# SensorNode.net
KiCad netlist of a schematic drawn in EAGLE
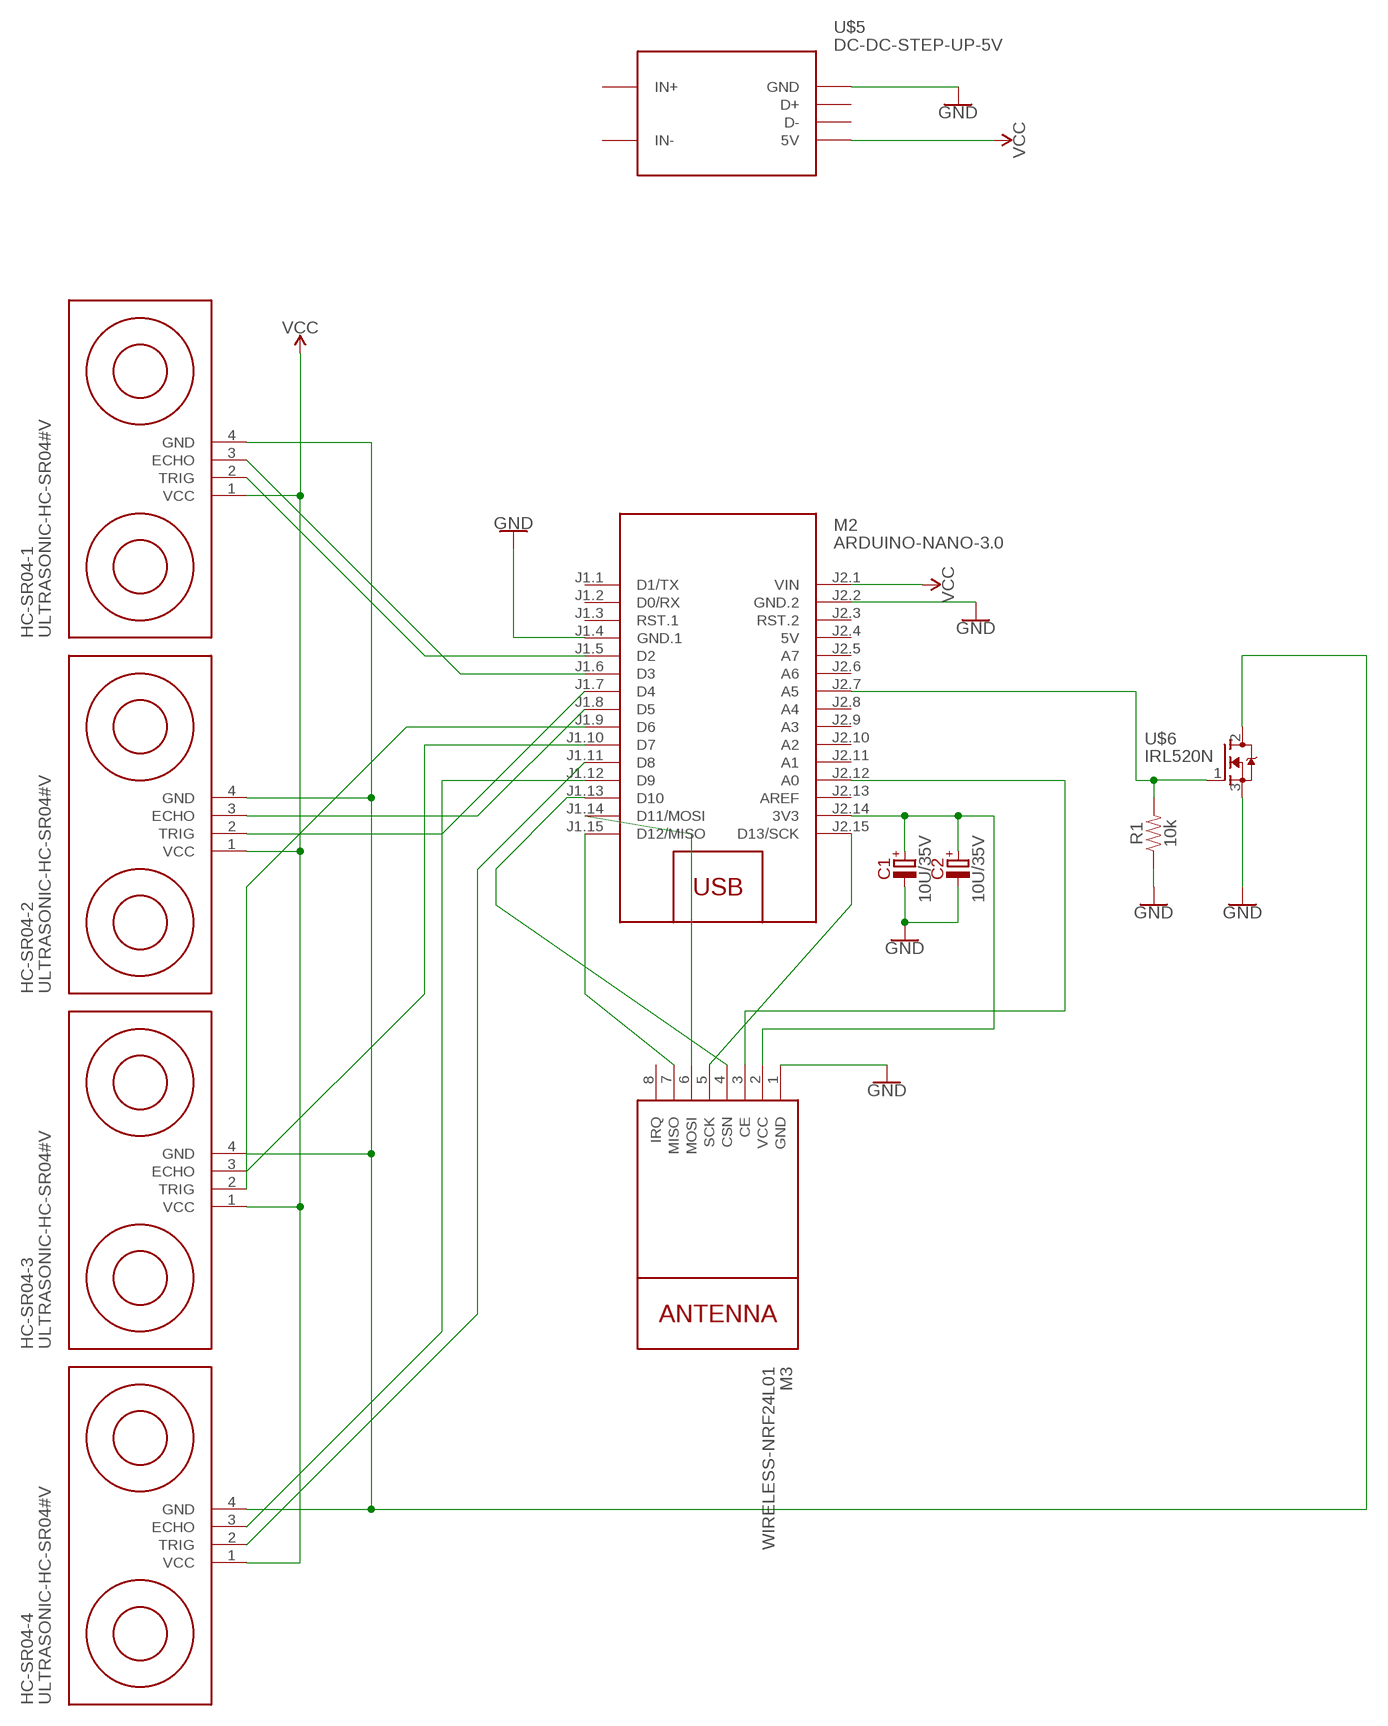
[diagram p0: schematic, sheet 1]

(export (version "E")
  (design (tool "Eeschema 10.0.6"))
  (components
    (comp (ref "C1")
      (value "10U/35V")
      (footprint "eagle-import:E2-5")
      (libsource (lib "eagle-import") (part "?10U/35V"))
    )
    (comp (ref "C2")
      (value "10U/35V")
      (footprint "eagle-import:E2-5")
      (libsource (lib "eagle-import") (part "?10U/35V"))
    )
    (comp (ref "HC-SR04-1")
      (value "ULTRASONIC-HC-SR04#V")
      (footprint "eagle-import:ULTRASONIC-HC-SR04#V")
      (libsource (lib "eagle-import") (part "ULTRASONIC-HC-SR04#V"))
    )
    (comp (ref "HC-SR04-2")
      (value "ULTRASONIC-HC-SR04#V")
      (footprint "eagle-import:ULTRASONIC-HC-SR04#V")
      (libsource (lib "eagle-import") (part "ULTRASONIC-HC-SR04#V"))
    )
    (comp (ref "HC-SR04-3")
      (value "ULTRASONIC-HC-SR04#V")
      (footprint "eagle-import:ULTRASONIC-HC-SR04#V")
      (libsource (lib "eagle-import") (part "ULTRASONIC-HC-SR04#V"))
    )
    (comp (ref "HC-SR04-4")
      (value "ULTRASONIC-HC-SR04#V")
      (footprint "eagle-import:ULTRASONIC-HC-SR04#V")
      (libsource (lib "eagle-import") (part "ULTRASONIC-HC-SR04#V"))
    )
    (comp (ref "M2")
      (value "ARDUINO-NANO-3.0")
      (footprint "eagle-import:ARDUINO-NANO-3.0")
      (libsource (lib "eagle-import") (part "ARDUINO-NANO-3.0"))
    )
    (comp (ref "M3")
      (value "WIRELESS-NRF24L01")
      (footprint "eagle-import:WIRELESS-NRF24L01")
      (libsource (lib "eagle-import") (part "WIRELESS-NRF24L01"))
    )
    (comp (ref "R1")
      (value "10k")
      (footprint "eagle-import:AXIAL-0.3-KIT")
      (libsource (lib "eagle-import") (part "10KOHM-HORIZ_KIT-1/4W-1%"))
    )
    (comp (ref "U$5")
      (value "DC-DC-STEP-UP-5V")
      (footprint "eagle-import:DC-DC-STEP-UP-5V")
      (libsource (lib "eagle-import") (part "DC-DC-STEP-UP-5V"))
    )
    (comp (ref "U$6")
      (value "IRL520N")
      (footprint "eagle-import:TO220-VERT")
      (fields (field (name "MF") "International Rectifier"))
      (libsource (lib "eagle-import") (part "IRL520N"))
    )
  )
  (nets
    (net (code "1") (name "/5V") (class "Default")
      (node (ref "M2") (pin "J2.4") (pinfunction "5V_J2.4") (pintype "power_in"))
    )
    (net (code "2") (name "/IN+") (class "Default")
      (node (ref "U$5") (pin "IN+") (pinfunction "IN+_IN+") (pintype "power_in"))
    )
    (net (code "3") (name "/IN-") (class "Default")
      (node (ref "U$5") (pin "IN-") (pinfunction "IN-_IN-") (pintype "power_in"))
    )
    (net (code "4") (name "GND") (class "Default")
      (node (ref "C1") (pin "-") (pinfunction "-_-") (pintype "passive"))
      (node (ref "C2") (pin "-") (pinfunction "-_-") (pintype "passive"))
      (node (ref "M2") (pin "J1.4") (pinfunction "GND.1_J1.4") (pintype "power_in"))
      (node (ref "M2") (pin "J2.2") (pinfunction "GND.2_J2.2") (pintype "power_in"))
      (node (ref "M3") (pin "1") (pinfunction "GND_1") (pintype "power_in"))
      (node (ref "R1") (pin "P$1") (pinfunction "1_P$1") (pintype "passive"))
      (node (ref "U$5") (pin "GND") (pinfunction "GND_GND") (pintype "bidirectional"))
      (node (ref "U$6") (pin "3") (pinfunction "S_3") (pintype "power_in"))
    )
    (net (code "5") (name "Net-(HC-SR04-1-ECHO)") (class "Default")
      (node (ref "HC-SR04-1") (pin "3") (pinfunction "ECHO_3") (pintype "output"))
      (node (ref "M2") (pin "J1.6") (pinfunction "D3_J1.6") (pintype "bidirectional"))
    )
    (net (code "6") (name "Net-(HC-SR04-1-GND)") (class "Default")
      (node (ref "HC-SR04-1") (pin "4") (pinfunction "GND_4") (pintype "power_in"))
      (node (ref "HC-SR04-2") (pin "4") (pinfunction "GND_4") (pintype "power_in"))
      (node (ref "HC-SR04-3") (pin "4") (pinfunction "GND_4") (pintype "power_in"))
      (node (ref "HC-SR04-4") (pin "4") (pinfunction "GND_4") (pintype "power_in"))
      (node (ref "U$6") (pin "2") (pinfunction "D_2") (pintype "power_in"))
    )
    (net (code "7") (name "Net-(HC-SR04-1-TRIG)") (class "Default")
      (node (ref "HC-SR04-1") (pin "2") (pinfunction "TRIG_2") (pintype "input"))
      (node (ref "M2") (pin "J1.5") (pinfunction "D2_J1.5") (pintype "bidirectional"))
    )
    (net (code "8") (name "Net-(HC-SR04-2-ECHO)") (class "Default")
      (node (ref "HC-SR04-2") (pin "3") (pinfunction "ECHO_3") (pintype "output"))
      (node (ref "M2") (pin "J1.8") (pinfunction "D5_J1.8") (pintype "bidirectional"))
    )
    (net (code "9") (name "Net-(HC-SR04-2-TRIG)") (class "Default")
      (node (ref "HC-SR04-2") (pin "2") (pinfunction "TRIG_2") (pintype "input"))
      (node (ref "M2") (pin "J1.7") (pinfunction "D4_J1.7") (pintype "bidirectional"))
    )
    (net (code "10") (name "Net-(HC-SR04-3-ECHO)") (class "Default")
      (node (ref "HC-SR04-3") (pin "3") (pinfunction "ECHO_3") (pintype "output"))
      (node (ref "M2") (pin "J1.10") (pinfunction "D7_J1.10") (pintype "bidirectional"))
    )
    (net (code "11") (name "Net-(HC-SR04-3-TRIG)") (class "Default")
      (node (ref "HC-SR04-3") (pin "2") (pinfunction "TRIG_2") (pintype "input"))
      (node (ref "M2") (pin "J1.9") (pinfunction "D6_J1.9") (pintype "bidirectional"))
    )
    (net (code "12") (name "Net-(HC-SR04-4-ECHO)") (class "Default")
      (node (ref "HC-SR04-4") (pin "3") (pinfunction "ECHO_3") (pintype "output"))
      (node (ref "M2") (pin "J1.12") (pinfunction "D9_J1.12") (pintype "bidirectional"))
    )
    (net (code "13") (name "Net-(HC-SR04-4-TRIG)") (class "Default")
      (node (ref "HC-SR04-4") (pin "2") (pinfunction "TRIG_2") (pintype "input"))
      (node (ref "M2") (pin "J1.11") (pinfunction "D8_J1.11") (pintype "bidirectional"))
    )
    (net (code "14") (name "Net-(M2-3V3)") (class "Default")
      (node (ref "C1") (pin "+") (pinfunction "+_+") (pintype "passive"))
      (node (ref "C2") (pin "+") (pinfunction "+_+") (pintype "passive"))
      (node (ref "M2") (pin "J2.14") (pinfunction "3V3_J2.14") (pintype "power_in"))
      (node (ref "M3") (pin "2") (pinfunction "VCC_2") (pintype "power_in"))
    )
    (net (code "15") (name "Net-(M2-A0)") (class "Default")
      (node (ref "M2") (pin "J2.12") (pinfunction "A0_J2.12") (pintype "bidirectional"))
      (node (ref "M3") (pin "3") (pinfunction "CE_3") (pintype "bidirectional"))
    )
    (net (code "16") (name "Net-(M2-A5)") (class "Default")
      (node (ref "M2") (pin "J2.7") (pinfunction "A5_J2.7") (pintype "bidirectional"))
      (node (ref "R1") (pin "P$2") (pinfunction "2_P$2") (pintype "passive"))
      (node (ref "U$6") (pin "1") (pinfunction "G_1") (pintype "power_in"))
    )
    (net (code "17") (name "Net-(M2-D10)") (class "Default")
      (node (ref "M2") (pin "J1.13") (pinfunction "D10_J1.13") (pintype "bidirectional"))
      (node (ref "M3") (pin "4") (pinfunction "CSN_4") (pintype "bidirectional"))
    )
    (net (code "18") (name "Net-(M2-D11{slash}MOSI)") (class "Default")
      (node (ref "M2") (pin "J1.14") (pinfunction "D11/MOSI_J1.14") (pintype "bidirectional"))
      (node (ref "M3") (pin "6") (pinfunction "MOSI_6") (pintype "bidirectional"))
    )
    (net (code "19") (name "Net-(M2-D12{slash}MISO)") (class "Default")
      (node (ref "M2") (pin "J1.15") (pinfunction "D12/MISO_J1.15") (pintype "bidirectional"))
      (node (ref "M3") (pin "7") (pinfunction "MISO_7") (pintype "bidirectional"))
    )
    (net (code "20") (name "Net-(M2-D13{slash}SCK)") (class "Default")
      (node (ref "M2") (pin "J2.15") (pinfunction "D13/SCK_J2.15") (pintype "bidirectional"))
      (node (ref "M3") (pin "5") (pinfunction "SCK_5") (pintype "bidirectional"))
    )
    (net (code "21") (name "VCC") (class "Default")
      (node (ref "HC-SR04-1") (pin "1") (pinfunction "VCC_1") (pintype "power_in"))
      (node (ref "HC-SR04-2") (pin "1") (pinfunction "VCC_1") (pintype "power_in"))
      (node (ref "HC-SR04-3") (pin "1") (pinfunction "VCC_1") (pintype "power_in"))
      (node (ref "HC-SR04-4") (pin "1") (pinfunction "VCC_1") (pintype "power_in"))
      (node (ref "M2") (pin "J2.1") (pinfunction "VIN_J2.1") (pintype "power_in"))
      (node (ref "U$5") (pin "5V") (pinfunction "5V_5V") (pintype "bidirectional"))
    )
    (net (code "22") (name "unconnected-(M2-A1-PadJ2.11)") (class "Default")
      (node (ref "M2") (pin "J2.11") (pinfunction "A1_J2.11") (pintype "bidirectional"))
    )
    (net (code "23") (name "unconnected-(M2-A2-PadJ2.10)") (class "Default")
      (node (ref "M2") (pin "J2.10") (pinfunction "A2_J2.10") (pintype "bidirectional"))
    )
    (net (code "24") (name "unconnected-(M2-A3-PadJ2.9)") (class "Default")
      (node (ref "M2") (pin "J2.9") (pinfunction "A3_J2.9") (pintype "bidirectional"))
    )
    (net (code "25") (name "unconnected-(M2-A4-PadJ2.8)") (class "Default")
      (node (ref "M2") (pin "J2.8") (pinfunction "A4_J2.8") (pintype "bidirectional"))
    )
    (net (code "26") (name "unconnected-(M2-A6-PadJ2.6)") (class "Default")
      (node (ref "M2") (pin "J2.6") (pinfunction "A6_J2.6") (pintype "bidirectional"))
    )
    (net (code "27") (name "unconnected-(M2-A7-PadJ2.5)") (class "Default")
      (node (ref "M2") (pin "J2.5") (pinfunction "A7_J2.5") (pintype "bidirectional"))
    )
    (net (code "28") (name "unconnected-(M2-AREF-PadJ2.13)") (class "Default")
      (node (ref "M2") (pin "J2.13") (pinfunction "AREF_J2.13") (pintype "bidirectional"))
    )
    (net (code "29") (name "unconnected-(M2-D0{slash}RX-PadJ1.2)") (class "Default")
      (node (ref "M2") (pin "J1.2") (pinfunction "D0/RX_J1.2") (pintype "bidirectional"))
    )
    (net (code "30") (name "unconnected-(M2-D1{slash}TX-PadJ1.1)") (class "Default")
      (node (ref "M2") (pin "J1.1") (pinfunction "D1/TX_J1.1") (pintype "bidirectional"))
    )
    (net (code "31") (name "unconnected-(M2-RST.1-PadJ1.3)") (class "Default")
      (node (ref "M2") (pin "J1.3") (pinfunction "RST.1_J1.3") (pintype "bidirectional"))
    )
    (net (code "32") (name "unconnected-(M2-RST.2-PadJ2.3)") (class "Default")
      (node (ref "M2") (pin "J2.3") (pinfunction "RST.2_J2.3") (pintype "bidirectional"))
    )
    (net (code "33") (name "unconnected-(M3-IRQ-Pad8)") (class "Default")
      (node (ref "M3") (pin "8") (pinfunction "IRQ_8") (pintype "bidirectional"))
    )
    (net (code "34") (name "unconnected-(U$5-PadD+)") (class "Default")
      (node (ref "U$5") (pin "D+") (pinfunction "D+_D+") (pintype "bidirectional"))
    )
    (net (code "35") (name "unconnected-(U$5-PadD-)") (class "Default")
      (node (ref "U$5") (pin "D-") (pinfunction "D-_D-") (pintype "bidirectional"))
    )
  )
)
